# 7_seg_display.net
KiCad netlist of a schematic drawn in Altium Designer
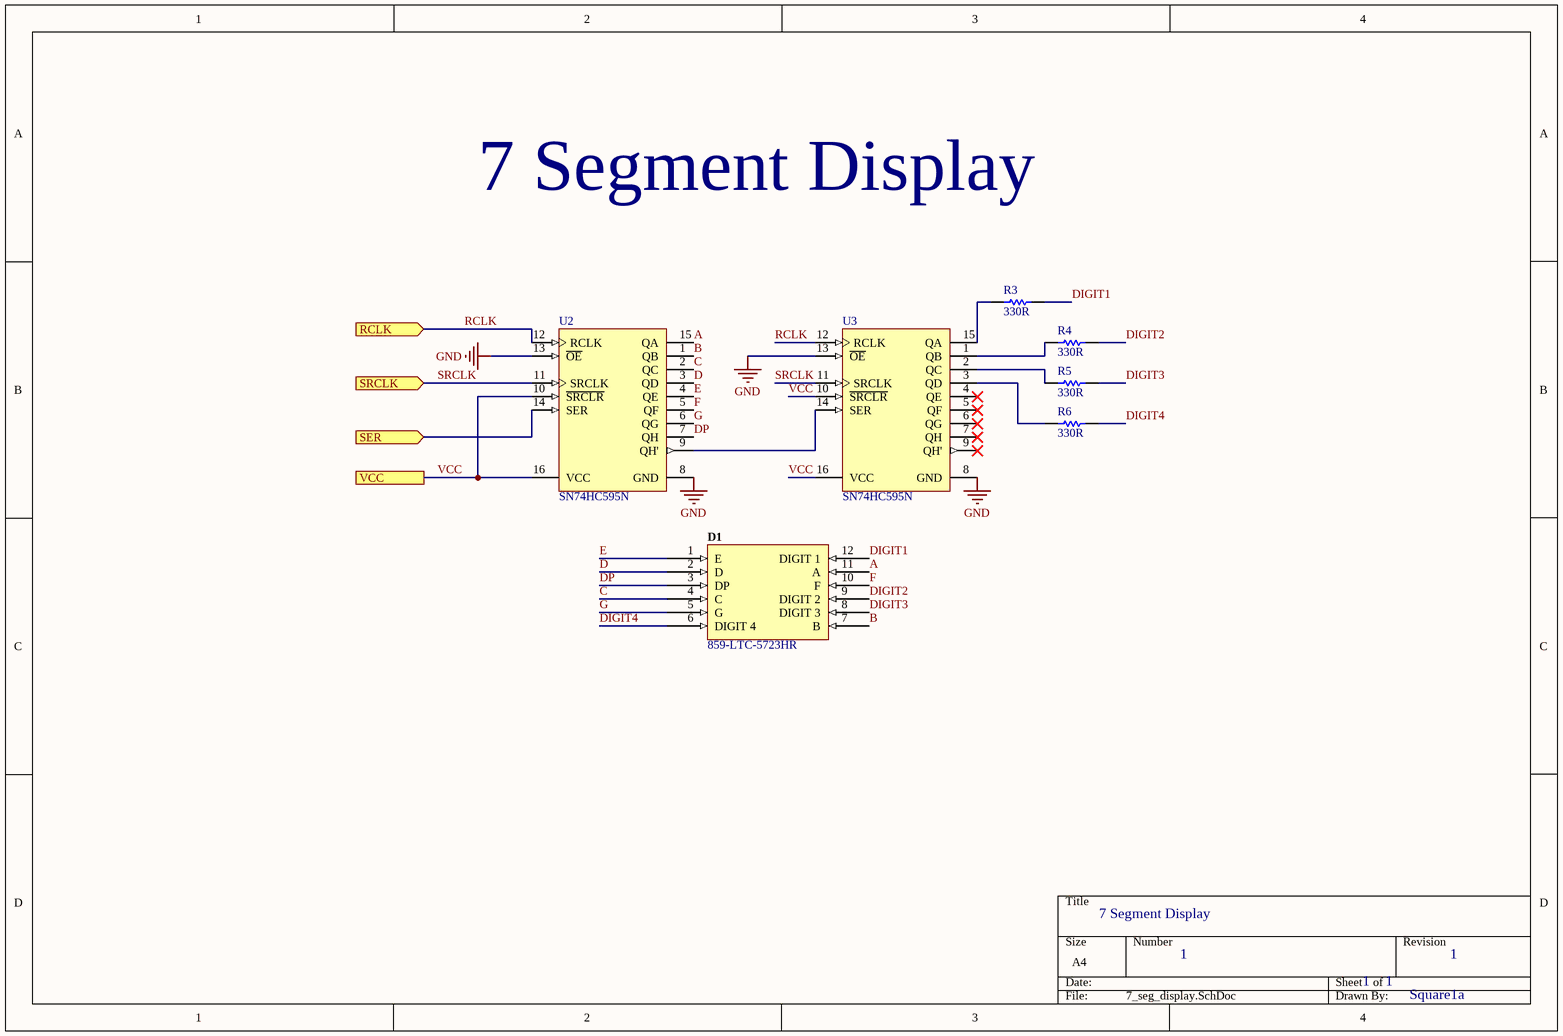
[diagram p0: 7_seg_display.SchDoc]

(export (version "E")
  (design (tool "Eeschema 10.0.6"))
  (components
    (comp (ref "D1")
      (value "4 digit display")
      (footprint "7 SEG DISPLAY (DIP12)")
      (description "Displays Segmented Panel 4DIGIT 32LED Hi-Eff. Red CC 12-Pin DIP")
      (fields
        (field (name "MANUFACTURER") "Vishay Lite-On")
        (field (name "MANUFACTURER PART NUMBER") "LTC-5723HR")
        (field (name "SUPPLIER PART NUMBER 1") "859-LTC-5723HR")
      )
      (libsource (lib "shared_schemLib") (part "LTC-5723HR"))
    )
    (comp (ref "R3")
      (value "330R")
      (footprint "RESA60-630X240")
      (description "Axial Resistor, 100 KOhm, +/- 1%, 0.25 W, -55 to 155 degC, 2-Pin THD, RoHS, Bulk")
      (fields (field (name "TOLERANCE") "1%"))
      (libsource (lib "Altium Content Vault") (part "RES-2"))
    )
    (comp (ref "R4")
      (value "330R")
      (footprint "RESA60-630X240")
      (description "Axial Resistor, 100 KOhm, +/- 1%, 0.25 W, -55 to 155 degC, 2-Pin THD, RoHS, Bulk")
      (fields (field (name "TOLERANCE") "1%"))
      (libsource (lib "Altium Content Vault") (part "RES-2"))
    )
    (comp (ref "R5")
      (value "330R")
      (footprint "RESA60-630X240")
      (description "Axial Resistor, 100 KOhm, +/- 1%, 0.25 W, -55 to 155 degC, 2-Pin THD, RoHS, Bulk")
      (fields (field (name "TOLERANCE") "1%"))
      (libsource (lib "Altium Content Vault") (part "RES-2"))
    )
    (comp (ref "R6")
      (value "330R")
      (footprint "RESA60-630X240")
      (description "Axial Resistor, 100 KOhm, +/- 1%, 0.25 W, -55 to 155 degC, 2-Pin THD, RoHS, Bulk")
      (fields (field (name "TOLERANCE") "1%"))
      (libsource (lib "Altium Content Vault") (part "RES-2"))
    )
    (comp (ref "U2")
      (value "SN74HC595N")
      (footprint "N0016A")
      (description "8-Bit Shift Registers With 3-State Output Registers, N0016A, TUBE")
      (fields
        (field (name "GENERIC PART NUMBER") "SN74HC595")
        (field (name "MANUFACTURER") "Texas Instruments")
      )
      (libsource (lib "Altium Content Vault") (part "TI-SN74XHCT595X_SN74LV595A-16"))
    )
    (comp (ref "U3")
      (value "SN74HC595N")
      (footprint "N0016A")
      (description "8-Bit Shift Registers With 3-State Output Registers, N0016A, TUBE")
      (fields
        (field (name "GENERIC PART NUMBER") "SN74HC595")
        (field (name "MANUFACTURER") "Texas Instruments")
      )
      (libsource (lib "Altium Content Vault") (part "TI-SN74XHCT595X_SN74LV595A-16"))
    )
  )
  (nets
    (net (code "1") (name "/A") (class "Default")
      (node (ref "D1") (pin "11") (pinfunction "A_11") (pintype "input"))
      (node (ref "U2") (pin "15") (pinfunction "QA_15") (pintype "tri_state"))
    )
    (net (code "2") (name "/B") (class "Default")
      (node (ref "D1") (pin "7") (pinfunction "B_7") (pintype "input"))
      (node (ref "U2") (pin "1") (pinfunction "QB_1") (pintype "tri_state"))
    )
    (net (code "3") (name "/C") (class "Default")
      (node (ref "D1") (pin "4") (pinfunction "C_4") (pintype "input"))
      (node (ref "U2") (pin "2") (pinfunction "QC_2") (pintype "tri_state"))
    )
    (net (code "4") (name "/D") (class "Default")
      (node (ref "D1") (pin "2") (pinfunction "D_2") (pintype "input"))
      (node (ref "U2") (pin "3") (pinfunction "QD_3") (pintype "tri_state"))
    )
    (net (code "5") (name "/DIGIT1") (class "Default")
      (node (ref "D1") (pin "12") (pinfunction "DIGIT_1_12") (pintype "input"))
      (node (ref "R3") (pin "1") (pinfunction "1_1") (pintype "passive"))
    )
    (net (code "6") (name "/DIGIT2") (class "Default")
      (node (ref "D1") (pin "9") (pinfunction "DIGIT_2_9") (pintype "input"))
      (node (ref "R4") (pin "1") (pinfunction "1_1") (pintype "passive"))
    )
    (net (code "7") (name "/DIGIT3") (class "Default")
      (node (ref "D1") (pin "8") (pinfunction "DIGIT_3_8") (pintype "input"))
      (node (ref "R5") (pin "1") (pinfunction "1_1") (pintype "passive"))
    )
    (net (code "8") (name "/DIGIT4") (class "Default")
      (node (ref "D1") (pin "6") (pinfunction "DIGIT_4_6") (pintype "input"))
      (node (ref "R6") (pin "1") (pinfunction "1_1") (pintype "passive"))
    )
    (net (code "9") (name "/DP") (class "Default")
      (node (ref "D1") (pin "3") (pinfunction "DP_3") (pintype "input"))
      (node (ref "U2") (pin "7") (pinfunction "QH_7") (pintype "tri_state"))
    )
    (net (code "10") (name "/E") (class "Default")
      (node (ref "D1") (pin "1") (pinfunction "E_1") (pintype "input"))
      (node (ref "U2") (pin "4") (pinfunction "QE_4") (pintype "tri_state"))
    )
    (net (code "11") (name "/F") (class "Default")
      (node (ref "D1") (pin "10") (pinfunction "F_10") (pintype "input"))
      (node (ref "U2") (pin "5") (pinfunction "QF_5") (pintype "tri_state"))
    )
    (net (code "12") (name "/G") (class "Default")
      (node (ref "D1") (pin "5") (pinfunction "G_5") (pintype "input"))
      (node (ref "U2") (pin "6") (pinfunction "QG_6") (pintype "tri_state"))
    )
    (net (code "13") (name "/RCLK") (class "Default")
      (node (ref "U2") (pin "12") (pinfunction "RCLK_12") (pintype "input"))
      (node (ref "U3") (pin "12") (pinfunction "RCLK_12") (pintype "input"))
    )
    (net (code "14") (name "/SER") (class "Default")
      (node (ref "U2") (pin "14") (pinfunction "SER_14") (pintype "input"))
    )
    (net (code "15") (name "/SRCLK") (class "Default")
      (node (ref "U2") (pin "11") (pinfunction "SRCLK_11") (pintype "input"))
      (node (ref "U3") (pin "11") (pinfunction "SRCLK_11") (pintype "input"))
    )
    (net (code "16") (name "/VCC") (class "Default")
      (node (ref "U2") (pin "10") (pinfunction "~{SRCLR}_10") (pintype "input"))
      (node (ref "U2") (pin "16") (pinfunction "VCC_16") (pintype "power_in"))
      (node (ref "U3") (pin "10") (pinfunction "~{SRCLR}_10") (pintype "input"))
      (node (ref "U3") (pin "16") (pinfunction "VCC_16") (pintype "power_in"))
    )
    (net (code "17") (name "GND") (class "Default")
      (node (ref "U2") (pin "13") (pinfunction "~{OE}_13") (pintype "input"))
      (node (ref "U2") (pin "8") (pinfunction "GND_8") (pintype "power_in"))
      (node (ref "U3") (pin "13") (pinfunction "~{OE}_13") (pintype "input"))
      (node (ref "U3") (pin "8") (pinfunction "GND_8") (pintype "power_in"))
    )
    (net (code "18") (name "Net-(U2-QH')") (class "Default")
      (node (ref "U2") (pin "9") (pinfunction "QH'_9") (pintype "output"))
      (node (ref "U3") (pin "14") (pinfunction "SER_14") (pintype "input"))
    )
    (net (code "19") (name "Net-(U3-QA)") (class "Default")
      (node (ref "R3") (pin "2") (pinfunction "2_2") (pintype "passive"))
      (node (ref "U3") (pin "15") (pinfunction "QA_15") (pintype "tri_state"))
    )
    (net (code "20") (name "Net-(U3-QB)") (class "Default")
      (node (ref "R4") (pin "2") (pinfunction "2_2") (pintype "passive"))
      (node (ref "U3") (pin "1") (pinfunction "QB_1") (pintype "tri_state"))
    )
    (net (code "21") (name "Net-(U3-QC)") (class "Default")
      (node (ref "R5") (pin "2") (pinfunction "2_2") (pintype "passive"))
      (node (ref "U3") (pin "2") (pinfunction "QC_2") (pintype "tri_state"))
    )
    (net (code "22") (name "Net-(U3-QD)") (class "Default")
      (node (ref "R6") (pin "2") (pinfunction "2_2") (pintype "passive"))
      (node (ref "U3") (pin "3") (pinfunction "QD_3") (pintype "tri_state"))
    )
    (net (code "23") (name "unconnected-(U3-QE-Pad4)") (class "Default")
      (node (ref "U3") (pin "4") (pinfunction "QE_4") (pintype "tri_state+no_connect"))
    )
    (net (code "24") (name "unconnected-(U3-QF-Pad5)") (class "Default")
      (node (ref "U3") (pin "5") (pinfunction "QF_5") (pintype "tri_state+no_connect"))
    )
    (net (code "25") (name "unconnected-(U3-QG-Pad6)") (class "Default")
      (node (ref "U3") (pin "6") (pinfunction "QG_6") (pintype "tri_state+no_connect"))
    )
    (net (code "26") (name "unconnected-(U3-QH'-Pad9)") (class "Default")
      (node (ref "U3") (pin "9") (pinfunction "QH'_9") (pintype "output+no_connect"))
    )
    (net (code "27") (name "unconnected-(U3-QH-Pad7)") (class "Default")
      (node (ref "U3") (pin "7") (pinfunction "QH_7") (pintype "tri_state+no_connect"))
    )
  )
)
